# uc1B.net
KiCad netlist of a schematic drawn in Altium Designer
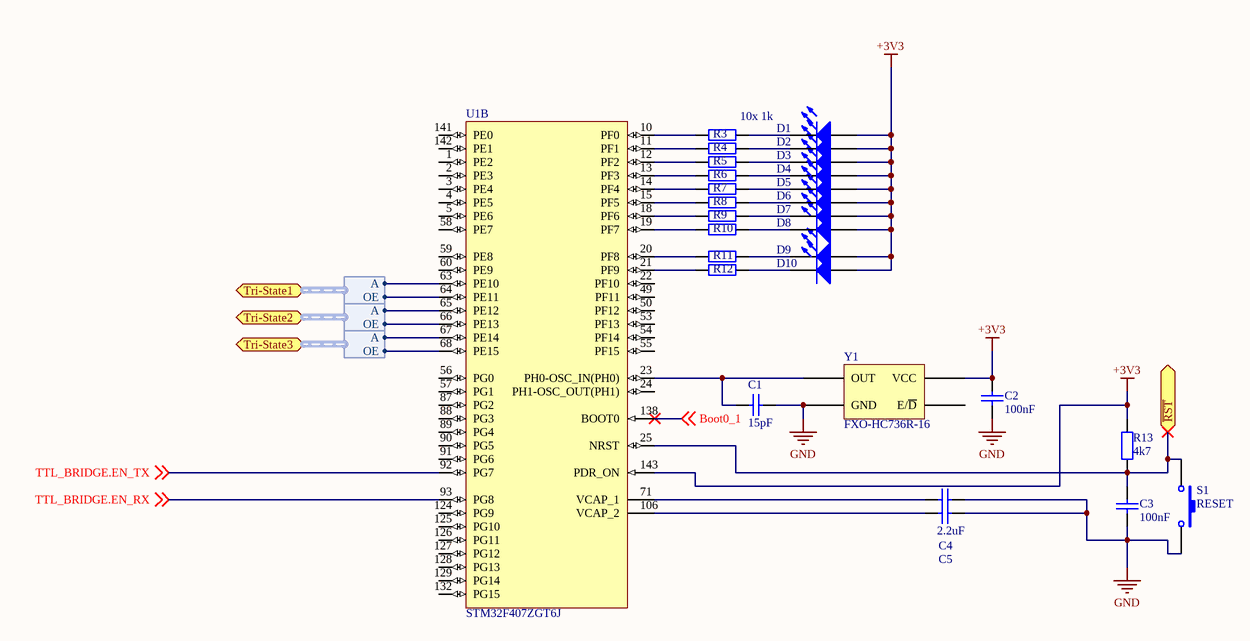
[diagram p0: uc1B.SchDoc]

(export (version "E")
  (design (tool "Eeschema 10.0.6"))
  (components
    (comp (ref "C1")
      (value "15pF")
      (footprint "C2012")
      (description "Capacitor")
      (fields
        (field (name "MANUFACTURER") "MULTICOMP")
        (field (name "MANUFACTURER PART NUMBER") "MC0805N150J500CT")
        (field (name "PUBLISHER") "Altium Limited")
      )
      (libsource (lib "Miscellaneous Devices") (part "Cap"))
    )
    (comp (ref "C2")
      (value "100nF")
      (footprint "C2012")
      (description "Capacitor")
      (fields (field (name "PUBLISHER") "Altium Limited"))
      (libsource (lib "Miscellaneous Devices") (part "Cap"))
    )
    (comp (ref "C3")
      (value "100nF")
      (footprint "C2012")
      (description "Capacitor")
      (fields
        (field (name "MANUFACTURER") "MULTICOMP")
        (field (name "MANUFACTURER PART NUMBER") "MC0805B104K500CT")
        (field (name "PUBLISHER") "Altium Limited")
      )
      (libsource (lib "Miscellaneous Devices") (part "Cap"))
    )
    (comp (ref "C4")
      (value "2.2uF")
      (footprint "C2012")
      (description "Capacitor")
      (fields
        (field (name "MANUFACTURER") "MULTICOMP")
        (field (name "MANUFACTURER PART NUMBER") "MC0805B225K250CT")
        (field (name "PUBLISHER") "Altium Limited")
      )
      (libsource (lib "Miscellaneous Devices") (part "Cap"))
    )
    (comp (ref "C5")
      (value "2.2uF")
      (footprint "C2012")
      (description "Capacitor")
      (fields
        (field (name "MANUFACTURER") "MULTICOMP")
        (field (name "MANUFACTURER PART NUMBER") "MC0805B225K250CT")
        (field (name "PUBLISHER") "Altium Limited")
      )
      (libsource (lib "Miscellaneous Devices") (part "Cap"))
    )
    (comp (ref "D1")
      (value "Green")
      (footprint "MLCC2")
      (description "Typical INFRARED GaAs LED")
      (fields
        (field (name "MANUFACTURER") "VISHAY")
        (field (name "MANUFACTURER PART NUMBER") "VLMC3100-GS08")
        (field (name "PUBLISHER") "Altium Limited")
      )
      (libsource (lib "Miscellaneous Devices") (part "LED0"))
    )
    (comp (ref "D2")
      (value "Green")
      (footprint "MLCC2")
      (description "Typical INFRARED GaAs LED")
      (fields
        (field (name "MANUFACTURER") "VISHAY")
        (field (name "MANUFACTURER PART NUMBER") "VLMC3100-GS08")
        (field (name "PUBLISHER") "Altium Limited")
      )
      (libsource (lib "Miscellaneous Devices") (part "LED0"))
    )
    (comp (ref "D3")
      (value "Green")
      (footprint "MLCC2")
      (description "Typical INFRARED GaAs LED")
      (fields
        (field (name "MANUFACTURER") "VISHAY")
        (field (name "MANUFACTURER PART NUMBER") "VLMC3100-GS08")
        (field (name "PUBLISHER") "Altium Limited")
      )
      (libsource (lib "Miscellaneous Devices") (part "LED0"))
    )
    (comp (ref "D4")
      (value "Green")
      (footprint "MLCC2")
      (description "Typical INFRARED GaAs LED")
      (fields
        (field (name "MANUFACTURER") "VISHAY")
        (field (name "MANUFACTURER PART NUMBER") "VLMC3100-GS08")
        (field (name "PUBLISHER") "Altium Limited")
      )
      (libsource (lib "Miscellaneous Devices") (part "LED0"))
    )
    (comp (ref "D5")
      (value "Green")
      (footprint "MLCC2")
      (description "Typical INFRARED GaAs LED")
      (fields
        (field (name "MANUFACTURER") "VISHAY")
        (field (name "MANUFACTURER PART NUMBER") "VLMC3100-GS08")
        (field (name "PUBLISHER") "Altium Limited")
      )
      (libsource (lib "Miscellaneous Devices") (part "LED0"))
    )
    (comp (ref "D6")
      (value "Green")
      (footprint "MLCC2")
      (description "Typical INFRARED GaAs LED")
      (fields
        (field (name "MANUFACTURER") "VISHAY")
        (field (name "MANUFACTURER PART NUMBER") "VLMC3100-GS08")
        (field (name "PUBLISHER") "Altium Limited")
      )
      (libsource (lib "Miscellaneous Devices") (part "LED0"))
    )
    (comp (ref "D7")
      (value "Green")
      (footprint "MLCC2")
      (description "Typical INFRARED GaAs LED")
      (fields
        (field (name "MANUFACTURER") "VISHAY")
        (field (name "MANUFACTURER PART NUMBER") "VLMC3100-GS08")
        (field (name "PUBLISHER") "Altium Limited")
      )
      (libsource (lib "Miscellaneous Devices") (part "LED0"))
    )
    (comp (ref "D8")
      (value "Green")
      (footprint "MLCC2")
      (description "Typical INFRARED GaAs LED")
      (fields
        (field (name "MANUFACTURER") "VISHAY")
        (field (name "MANUFACTURER PART NUMBER") "VLMC3100-GS08")
        (field (name "PUBLISHER") "Altium Limited")
      )
      (libsource (lib "Miscellaneous Devices") (part "LED0"))
    )
    (comp (ref "D9")
      (value "Green")
      (footprint "MLCC2")
      (description "Typical INFRARED GaAs LED")
      (fields
        (field (name "MANUFACTURER") "VISHAY")
        (field (name "MANUFACTURER PART NUMBER") "VLMC3100-GS08")
        (field (name "PUBLISHER") "Altium Limited")
      )
      (libsource (lib "Miscellaneous Devices") (part "LED0"))
    )
    (comp (ref "D10")
      (value "Green")
      (footprint "MLCC2")
      (description "Typical INFRARED GaAs LED")
      (fields
        (field (name "MANUFACTURER") "VISHAY")
        (field (name "MANUFACTURER PART NUMBER") "VLMC3100-GS08")
        (field (name "PUBLISHER") "Altium Limited")
      )
      (libsource (lib "Miscellaneous Devices") (part "LED0"))
    )
    (comp (ref "R3")
      (value "1k")
      (footprint "R2012")
      (description "Resistor")
      (fields
        (field (name "MANUFACTURER") "MULTICOMP")
        (field (name "MANUFACTURER PART NUMBER") "MC01W0805110K")
        (field (name "PUBLISHER") "Altium Limited")
      )
      (libsource (lib "Miscellaneous Devices") (part "Res2"))
    )
    (comp (ref "R4")
      (value "1k")
      (footprint "R2012")
      (description "Resistor")
      (fields
        (field (name "MANUFACTURER") "MULTICOMP")
        (field (name "MANUFACTURER PART NUMBER") "MC01W0805110K")
        (field (name "PUBLISHER") "Altium Limited")
      )
      (libsource (lib "Miscellaneous Devices") (part "Res2"))
    )
    (comp (ref "R5")
      (value "1k")
      (footprint "R2012")
      (description "Resistor")
      (fields
        (field (name "MANUFACTURER") "MULTICOMP")
        (field (name "MANUFACTURER PART NUMBER") "MC01W0805110K")
        (field (name "PUBLISHER") "Altium Limited")
      )
      (libsource (lib "Miscellaneous Devices") (part "Res2"))
    )
    (comp (ref "R6")
      (value "1k")
      (footprint "R2012")
      (description "Resistor")
      (fields
        (field (name "MANUFACTURER") "MULTICOMP")
        (field (name "MANUFACTURER PART NUMBER") "MC01W0805110K")
        (field (name "PUBLISHER") "Altium Limited")
      )
      (libsource (lib "Miscellaneous Devices") (part "Res2"))
    )
    (comp (ref "R7")
      (value "1k")
      (footprint "R2012")
      (description "Resistor")
      (fields
        (field (name "MANUFACTURER") "MULTICOMP")
        (field (name "MANUFACTURER PART NUMBER") "MC01W0805110K")
        (field (name "PUBLISHER") "Altium Limited")
      )
      (libsource (lib "Miscellaneous Devices") (part "Res2"))
    )
    (comp (ref "R8")
      (value "1k")
      (footprint "R2012")
      (description "Resistor")
      (fields
        (field (name "MANUFACTURER") "MULTICOMP")
        (field (name "MANUFACTURER PART NUMBER") "MC01W0805110K")
        (field (name "PUBLISHER") "Altium Limited")
      )
      (libsource (lib "Miscellaneous Devices") (part "Res2"))
    )
    (comp (ref "R9")
      (value "1k")
      (footprint "R2012")
      (description "Resistor")
      (fields
        (field (name "MANUFACTURER") "MULTICOMP")
        (field (name "MANUFACTURER PART NUMBER") "MC01W0805110K")
        (field (name "PUBLISHER") "Altium Limited")
      )
      (libsource (lib "Miscellaneous Devices") (part "Res2"))
    )
    (comp (ref "R10")
      (value "1k")
      (footprint "R2012")
      (description "Resistor")
      (fields
        (field (name "MANUFACTURER") "MULTICOMP")
        (field (name "MANUFACTURER PART NUMBER") "MC01W0805110K")
        (field (name "PUBLISHER") "Altium Limited")
      )
      (libsource (lib "Miscellaneous Devices") (part "Res2"))
    )
    (comp (ref "R11")
      (value "1k")
      (footprint "R2012")
      (description "Resistor")
      (fields
        (field (name "MANUFACTURER") "MULTICOMP")
        (field (name "MANUFACTURER PART NUMBER") "MC01W0805110K")
        (field (name "PUBLISHER") "Altium Limited")
      )
      (libsource (lib "Miscellaneous Devices") (part "Res2"))
    )
    (comp (ref "R12")
      (value "1k")
      (footprint "R2012")
      (description "Resistor")
      (fields
        (field (name "MANUFACTURER") "MULTICOMP")
        (field (name "MANUFACTURER PART NUMBER") "MC01W0805110K")
        (field (name "PUBLISHER") "Altium Limited")
      )
      (libsource (lib "Miscellaneous Devices") (part "Res2"))
    )
    (comp (ref "R13")
      (value "4k7")
      (footprint "R2012")
      (description "Resistor")
      (fields
        (field (name "MANUFACTURER") "MULTICOMP")
        (field (name "MANUFACTURER PART NUMBER") "MC01W080514K7")
        (field (name "PUBLISHER") "Altium Limited")
      )
      (libsource (lib "") (part "Res2_1"))
    )
    (comp (ref "S1")
      (value "RESET")
      (footprint "SWITCH")
      (description "Switch")
      (fields (field (name "PUBLISHER") "Altium Limited"))
      (libsource (lib "Miscellaneous Devices") (part "SW-PB"))
    )
    (comp (ref "U1")
      (value "STM32F407ZGT6J")
      (footprint "STM-LQFP144_M")
      (fields (field (name "MANUFACTURER") "STMicroelectronics"))
      (libsource (lib "Altium Content Vault") (part "CMP-0243-00063-2"))
    )
    (comp (ref "Y1")
      (value "FXO-HC736R-16")
      (footprint "FXO-HC73")
      (description "Oscillator with Enable Input")
      (fields (field (name "MANUFACTURER") "FOX ELECTRONICS"))
      (libsource (lib "bitbots") (part "Oszillator"))
    )
  )
  (nets
    (net (code "3") (name "+3V3") (class "Default")
      (node (ref "C2") (pin "1") (pinfunction "1_1") (pintype "passive"))
      (node (ref "D1") (pin "1") (pinfunction "A_1") (pintype "passive"))
      (node (ref "D10") (pin "1") (pinfunction "A_1") (pintype "passive"))
      (node (ref "D2") (pin "1") (pinfunction "A_1") (pintype "passive"))
      (node (ref "D3") (pin "1") (pinfunction "A_1") (pintype "passive"))
      (node (ref "D4") (pin "1") (pinfunction "A_1") (pintype "passive"))
      (node (ref "D5") (pin "1") (pinfunction "A_1") (pintype "passive"))
      (node (ref "D6") (pin "1") (pinfunction "A_1") (pintype "passive"))
      (node (ref "D7") (pin "1") (pinfunction "A_1") (pintype "passive"))
      (node (ref "D8") (pin "1") (pinfunction "A_1") (pintype "passive"))
      (node (ref "D9") (pin "1") (pinfunction "A_1") (pintype "passive"))
      (node (ref "R13") (pin "1") (pinfunction "1_1") (pintype "passive"))
      (node (ref "U1") (pin "143") (pinfunction "PDR_ON_143") (pintype "input"))
      (node (ref "Y1") (pin "4") (pinfunction "VCC_4") (pintype "passive"))
    )
    (net (code "4") (name "/RST") (class "Default")
      (node (ref "C3") (pin "2") (pinfunction "2_2") (pintype "passive"))
      (node (ref "R13") (pin "2") (pinfunction "2_2") (pintype "passive"))
      (node (ref "S1") (pin "1") (pinfunction "1_1") (pintype "passive"))
      (node (ref "U1") (pin "25") (pinfunction "NRST_25") (pintype "bidirectional"))
    )
    (net (code "7") (name "Boot0_1") (class "Default")
      (node (ref "U1") (pin "138") (pinfunction "BOOT0_138") (pintype "input"))
    )
    (net (code "8") (name "GND") (class "Default")
      (node (ref "C1") (pin "1") (pinfunction "1_1") (pintype "passive"))
      (node (ref "C2") (pin "2") (pinfunction "2_2") (pintype "passive"))
      (node (ref "C3") (pin "1") (pinfunction "1_1") (pintype "passive"))
      (node (ref "C4") (pin "2") (pinfunction "2_2") (pintype "passive"))
      (node (ref "C5") (pin "2") (pinfunction "2_2") (pintype "passive"))
      (node (ref "S1") (pin "2") (pinfunction "2_2") (pintype "passive"))
      (node (ref "Y1") (pin "2") (pinfunction "GND_2") (pintype "passive"))
    )
    (net (code "9") (name "Net-(D1-K)") (class "Default")
      (node (ref "D1") (pin "2") (pinfunction "K_2") (pintype "passive"))
      (node (ref "R3") (pin "2") (pinfunction "2_2") (pintype "passive"))
    )
    (net (code "10") (name "Net-(D2-K)") (class "Default")
      (node (ref "D2") (pin "2") (pinfunction "K_2") (pintype "passive"))
      (node (ref "R4") (pin "2") (pinfunction "2_2") (pintype "passive"))
    )
    (net (code "11") (name "Net-(D3-K)") (class "Default")
      (node (ref "D3") (pin "2") (pinfunction "K_2") (pintype "passive"))
      (node (ref "R5") (pin "2") (pinfunction "2_2") (pintype "passive"))
    )
    (net (code "12") (name "Net-(D4-K)") (class "Default")
      (node (ref "D4") (pin "2") (pinfunction "K_2") (pintype "passive"))
      (node (ref "R6") (pin "2") (pinfunction "2_2") (pintype "passive"))
    )
    (net (code "13") (name "Net-(D5-K)") (class "Default")
      (node (ref "D5") (pin "2") (pinfunction "K_2") (pintype "passive"))
      (node (ref "R7") (pin "2") (pinfunction "2_2") (pintype "passive"))
    )
    (net (code "14") (name "Net-(D6-K)") (class "Default")
      (node (ref "D6") (pin "2") (pinfunction "K_2") (pintype "passive"))
      (node (ref "R8") (pin "2") (pinfunction "2_2") (pintype "passive"))
    )
    (net (code "15") (name "Net-(D7-K)") (class "Default")
      (node (ref "D7") (pin "2") (pinfunction "K_2") (pintype "passive"))
      (node (ref "R9") (pin "2") (pinfunction "2_2") (pintype "passive"))
    )
    (net (code "16") (name "Net-(D8-K)") (class "Default")
      (node (ref "D8") (pin "2") (pinfunction "K_2") (pintype "passive"))
      (node (ref "R10") (pin "2") (pinfunction "2_2") (pintype "passive"))
    )
    (net (code "17") (name "Net-(D9-K)") (class "Default")
      (node (ref "D9") (pin "2") (pinfunction "K_2") (pintype "passive"))
      (node (ref "R11") (pin "2") (pinfunction "2_2") (pintype "passive"))
    )
    (net (code "18") (name "Net-(D10-K)") (class "Default")
      (node (ref "D10") (pin "2") (pinfunction "K_2") (pintype "passive"))
      (node (ref "R12") (pin "2") (pinfunction "2_2") (pintype "passive"))
    )
    (net (code "19") (name "Net-(U1B-PF0)") (class "Default")
      (node (ref "R3") (pin "1") (pinfunction "1_1") (pintype "passive"))
      (node (ref "U1") (pin "10") (pinfunction "PF0_10") (pintype "bidirectional"))
    )
    (net (code "20") (name "Net-(U1B-PF1)") (class "Default")
      (node (ref "R4") (pin "1") (pinfunction "1_1") (pintype "passive"))
      (node (ref "U1") (pin "11") (pinfunction "PF1_11") (pintype "bidirectional"))
    )
    (net (code "21") (name "Net-(U1B-PF2)") (class "Default")
      (node (ref "R5") (pin "1") (pinfunction "1_1") (pintype "passive"))
      (node (ref "U1") (pin "12") (pinfunction "PF2_12") (pintype "bidirectional"))
    )
    (net (code "22") (name "Net-(U1B-PF3)") (class "Default")
      (node (ref "R6") (pin "1") (pinfunction "1_1") (pintype "passive"))
      (node (ref "U1") (pin "13") (pinfunction "PF3_13") (pintype "bidirectional"))
    )
    (net (code "23") (name "Net-(U1B-PF4)") (class "Default")
      (node (ref "R7") (pin "1") (pinfunction "1_1") (pintype "passive"))
      (node (ref "U1") (pin "14") (pinfunction "PF4_14") (pintype "bidirectional"))
    )
    (net (code "24") (name "Net-(U1B-PF5)") (class "Default")
      (node (ref "R8") (pin "1") (pinfunction "1_1") (pintype "passive"))
      (node (ref "U1") (pin "15") (pinfunction "PF5_15") (pintype "bidirectional"))
    )
    (net (code "25") (name "Net-(U1B-PF6)") (class "Default")
      (node (ref "R9") (pin "1") (pinfunction "1_1") (pintype "passive"))
      (node (ref "U1") (pin "18") (pinfunction "PF6_18") (pintype "bidirectional"))
    )
    (net (code "26") (name "Net-(U1B-PF7)") (class "Default")
      (node (ref "R10") (pin "1") (pinfunction "1_1") (pintype "passive"))
      (node (ref "U1") (pin "19") (pinfunction "PF7_19") (pintype "bidirectional"))
    )
    (net (code "27") (name "Net-(U1B-PF8)") (class "Default")
      (node (ref "R11") (pin "1") (pinfunction "1_1") (pintype "passive"))
      (node (ref "U1") (pin "20") (pinfunction "PF8_20") (pintype "bidirectional"))
    )
    (net (code "28") (name "Net-(U1B-PF9)") (class "Default")
      (node (ref "R12") (pin "1") (pinfunction "1_1") (pintype "passive"))
      (node (ref "U1") (pin "21") (pinfunction "PF9_21") (pintype "bidirectional"))
    )
    (net (code "29") (name "Net-(U1B-PH0-OSC_IN(PH0))") (class "Default")
      (node (ref "C1") (pin "2") (pinfunction "2_2") (pintype "passive"))
      (node (ref "U1") (pin "23") (pinfunction "PH0-OSC_IN(PH0)_23") (pintype "bidirectional"))
      (node (ref "Y1") (pin "3") (pinfunction "OUT_3") (pintype "passive"))
    )
    (net (code "30") (name "Net-(U1B-VCAP_1)") (class "Default")
      (node (ref "C4") (pin "1") (pinfunction "1_1") (pintype "passive"))
      (node (ref "U1") (pin "71") (pinfunction "VCAP_1_71") (pintype "power_in"))
    )
    (net (code "31") (name "Net-(U1B-VCAP_2)") (class "Default")
      (node (ref "C5") (pin "1") (pinfunction "1_1") (pintype "passive"))
      (node (ref "U1") (pin "106") (pinfunction "VCAP_2_106") (pintype "power_in"))
    )
    (net (code "32") (name "TTL_BRIDGE.EN_RX") (class "Default")
      (node (ref "U1") (pin "93") (pinfunction "PG8_93") (pintype "bidirectional"))
    )
    (net (code "33") (name "TTL_BRIDGE.EN_TX") (class "Default")
      (node (ref "U1") (pin "92") (pinfunction "PG7_92") (pintype "bidirectional"))
    )
    (net (code "34") (name "unconnected-(U1B-PE0-Pad141)") (class "Default")
      (node (ref "U1") (pin "141") (pinfunction "PE0_141") (pintype "bidirectional"))
    )
    (net (code "35") (name "unconnected-(U1B-PE1-Pad142)") (class "Default")
      (node (ref "U1") (pin "142") (pinfunction "PE1_142") (pintype "bidirectional"))
    )
    (net (code "36") (name "unconnected-(U1B-PE2-Pad1)") (class "Default")
      (node (ref "U1") (pin "1") (pinfunction "PE2_1") (pintype "bidirectional"))
    )
    (net (code "37") (name "unconnected-(U1B-PE3-Pad2)") (class "Default")
      (node (ref "U1") (pin "2") (pinfunction "PE3_2") (pintype "bidirectional"))
    )
    (net (code "38") (name "unconnected-(U1B-PE4-Pad3)") (class "Default")
      (node (ref "U1") (pin "3") (pinfunction "PE4_3") (pintype "bidirectional"))
    )
    (net (code "39") (name "unconnected-(U1B-PE5-Pad4)") (class "Default")
      (node (ref "U1") (pin "4") (pinfunction "PE5_4") (pintype "bidirectional"))
    )
    (net (code "40") (name "unconnected-(U1B-PE6-Pad5)") (class "Default")
      (node (ref "U1") (pin "5") (pinfunction "PE6_5") (pintype "bidirectional"))
    )
    (net (code "41") (name "unconnected-(U1B-PE7-Pad58)") (class "Default")
      (node (ref "U1") (pin "58") (pinfunction "PE7_58") (pintype "bidirectional"))
    )
    (net (code "42") (name "unconnected-(U1B-PE8-Pad59)") (class "Default")
      (node (ref "U1") (pin "59") (pinfunction "PE8_59") (pintype "bidirectional"))
    )
    (net (code "43") (name "unconnected-(U1B-PE9-Pad60)") (class "Default")
      (node (ref "U1") (pin "60") (pinfunction "PE9_60") (pintype "bidirectional"))
    )
    (net (code "44") (name "unconnected-(U1B-PE10-Pad63)") (class "Default")
      (node (ref "U1") (pin "63") (pinfunction "PE10_63") (pintype "bidirectional"))
    )
    (net (code "45") (name "unconnected-(U1B-PE11-Pad64)") (class "Default")
      (node (ref "U1") (pin "64") (pinfunction "PE11_64") (pintype "bidirectional"))
    )
    (net (code "46") (name "unconnected-(U1B-PE12-Pad65)") (class "Default")
      (node (ref "U1") (pin "65") (pinfunction "PE12_65") (pintype "bidirectional"))
    )
    (net (code "47") (name "unconnected-(U1B-PE13-Pad66)") (class "Default")
      (node (ref "U1") (pin "66") (pinfunction "PE13_66") (pintype "bidirectional"))
    )
    (net (code "48") (name "unconnected-(U1B-PE14-Pad67)") (class "Default")
      (node (ref "U1") (pin "67") (pinfunction "PE14_67") (pintype "bidirectional"))
    )
    (net (code "49") (name "unconnected-(U1B-PE15-Pad68)") (class "Default")
      (node (ref "U1") (pin "68") (pinfunction "PE15_68") (pintype "bidirectional"))
    )
    (net (code "50") (name "unconnected-(U1B-PF10-Pad22)") (class "Default")
      (node (ref "U1") (pin "22") (pinfunction "PF10_22") (pintype "bidirectional"))
    )
    (net (code "51") (name "unconnected-(U1B-PF11-Pad49)") (class "Default")
      (node (ref "U1") (pin "49") (pinfunction "PF11_49") (pintype "bidirectional"))
    )
    (net (code "52") (name "unconnected-(U1B-PF12-Pad50)") (class "Default")
      (node (ref "U1") (pin "50") (pinfunction "PF12_50") (pintype "bidirectional"))
    )
    (net (code "53") (name "unconnected-(U1B-PF13-Pad53)") (class "Default")
      (node (ref "U1") (pin "53") (pinfunction "PF13_53") (pintype "bidirectional"))
    )
    (net (code "54") (name "unconnected-(U1B-PF14-Pad54)") (class "Default")
      (node (ref "U1") (pin "54") (pinfunction "PF14_54") (pintype "bidirectional"))
    )
    (net (code "55") (name "unconnected-(U1B-PF15-Pad55)") (class "Default")
      (node (ref "U1") (pin "55") (pinfunction "PF15_55") (pintype "bidirectional"))
    )
    (net (code "56") (name "unconnected-(U1B-PG0-Pad56)") (class "Default")
      (node (ref "U1") (pin "56") (pinfunction "PG0_56") (pintype "bidirectional"))
    )
    (net (code "57") (name "unconnected-(U1B-PG1-Pad57)") (class "Default")
      (node (ref "U1") (pin "57") (pinfunction "PG1_57") (pintype "bidirectional"))
    )
    (net (code "58") (name "unconnected-(U1B-PG2-Pad87)") (class "Default")
      (node (ref "U1") (pin "87") (pinfunction "PG2_87") (pintype "bidirectional"))
    )
    (net (code "59") (name "unconnected-(U1B-PG3-Pad88)") (class "Default")
      (node (ref "U1") (pin "88") (pinfunction "PG3_88") (pintype "bidirectional"))
    )
    (net (code "60") (name "unconnected-(U1B-PG4-Pad89)") (class "Default")
      (node (ref "U1") (pin "89") (pinfunction "PG4_89") (pintype "bidirectional"))
    )
    (net (code "61") (name "unconnected-(U1B-PG5-Pad90)") (class "Default")
      (node (ref "U1") (pin "90") (pinfunction "PG5_90") (pintype "bidirectional"))
    )
    (net (code "62") (name "unconnected-(U1B-PG6-Pad91)") (class "Default")
      (node (ref "U1") (pin "91") (pinfunction "PG6_91") (pintype "bidirectional"))
    )
    (net (code "63") (name "unconnected-(U1B-PG9-Pad124)") (class "Default")
      (node (ref "U1") (pin "124") (pinfunction "PG9_124") (pintype "bidirectional"))
    )
    (net (code "64") (name "unconnected-(U1B-PG10-Pad125)") (class "Default")
      (node (ref "U1") (pin "125") (pinfunction "PG10_125") (pintype "bidirectional"))
    )
    (net (code "65") (name "unconnected-(U1B-PG11-Pad126)") (class "Default")
      (node (ref "U1") (pin "126") (pinfunction "PG11_126") (pintype "bidirectional"))
    )
    (net (code "66") (name "unconnected-(U1B-PG12-Pad127)") (class "Default")
      (node (ref "U1") (pin "127") (pinfunction "PG12_127") (pintype "bidirectional"))
    )
    (net (code "67") (name "unconnected-(U1B-PG13-Pad128)") (class "Default")
      (node (ref "U1") (pin "128") (pinfunction "PG13_128") (pintype "bidirectional"))
    )
    (net (code "68") (name "unconnected-(U1B-PG14-Pad129)") (class "Default")
      (node (ref "U1") (pin "129") (pinfunction "PG14_129") (pintype "bidirectional"))
    )
    (net (code "69") (name "unconnected-(U1B-PG15-Pad132)") (class "Default")
      (node (ref "U1") (pin "132") (pinfunction "PG15_132") (pintype "bidirectional"))
    )
    (net (code "70") (name "unconnected-(U1B-PH1-OSC_OUT(PH1)-Pad24)") (class "Default")
      (node (ref "U1") (pin "24") (pinfunction "PH1-OSC_OUT(PH1)_24") (pintype "bidirectional"))
    )
    (net (code "71") (name "unconnected-(Y1-E{slash}~{D}-Pad1)") (class "Default")
      (node (ref "Y1") (pin "1") (pinfunction "E/~{D}_1") (pintype "passive"))
    )
  )
)
